# design.net
KiCad netlist of a schematic drawn in Altium Designer
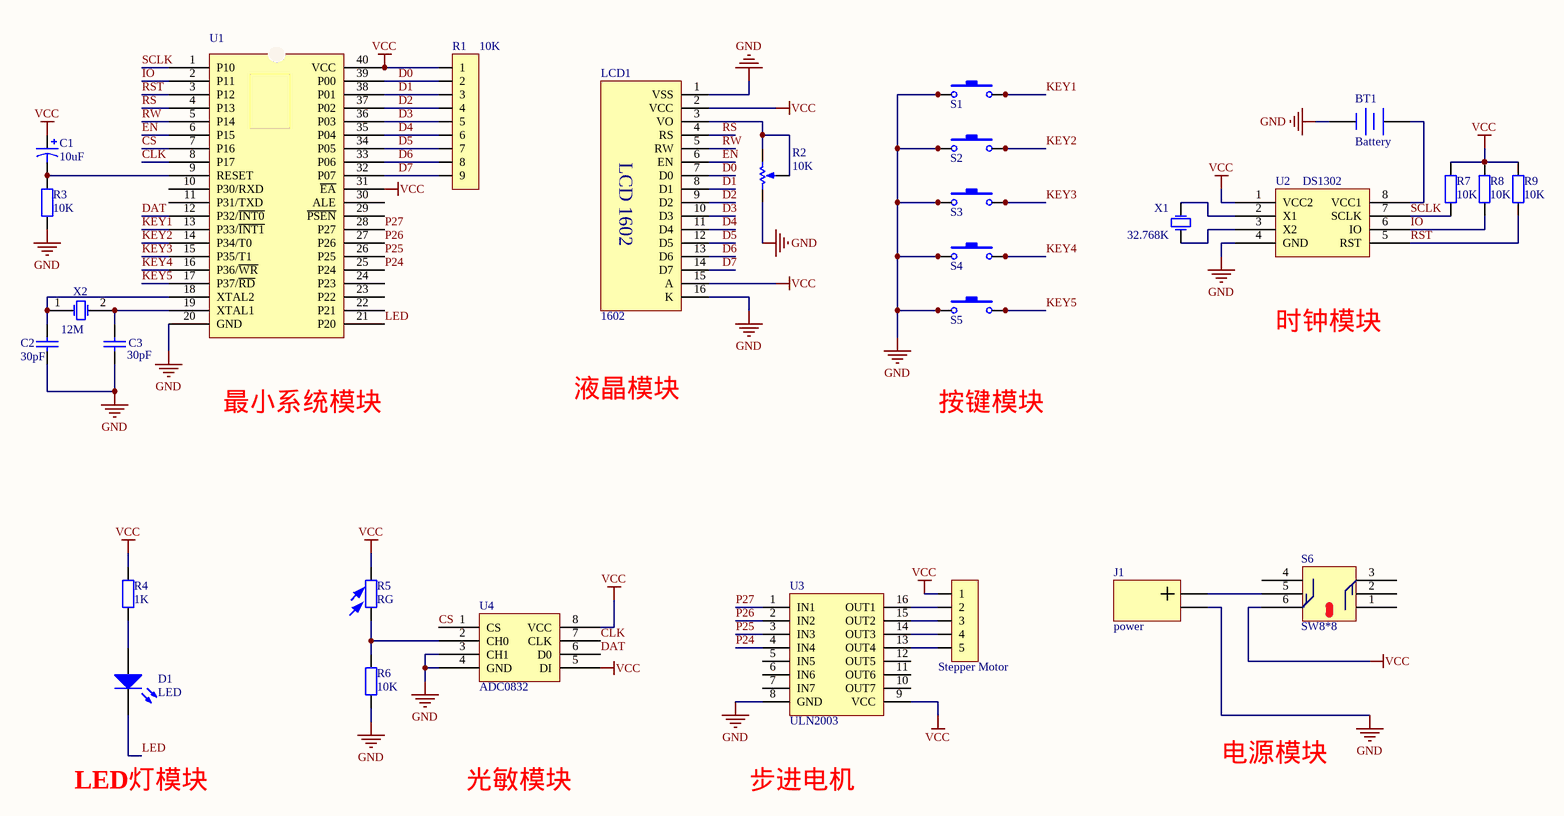
[diagram p0: 硬件电路.SchDoc]

(export (version "E")
  (design (tool "Eeschema 10.0.6"))
  (components
    (comp (ref "BT1")
      (value "Battery")
      (footprint "DCZ--DCBT_3V")
      (libsource (lib "MANUAL") (part "Battery"))
    )
    (comp (ref "C1") (value "10uF") (footprint "DR--CRB-2.54/5MM") (libsource (lib "Schlib") (part "CAP_2")))
    (comp (ref "C2") (value "30pF") (footprint "DR--CCP-4X5") (libsource (lib "Schlib") (part "CAP")))
    (comp (ref "C3") (value "30pF") (footprint "DR--CCP-4X5") (libsource (lib "Schlib") (part "CAP")))
    (comp (ref "D1") (value "LED") (footprint "EJG--LED5mm") (libsource (lib "MANUAL") (part "LED")))
    (comp (ref "J1") (value "power") (footprint "DYZ--DC002") (libsource (lib "Schlib") (part "DC5.5")))
    (comp (ref "J2")
      (value "Stepper Motor")
      (footprint "HDR1X5")
      (libsource (lib "Factory") (part "HEARDER5"))
    )
    (comp (ref "LCD1") (value "1602") (footprint "YJ--LCD1602") (libsource (lib "MANUAL") (part "1602")))
    (comp (ref "R1") (value "10K") (footprint "DZ--Rpz09") (libsource (lib "Schlib") (part "Header9")))
    (comp (ref "R2") (value "10K") (footprint "DZ--R065") (libsource (lib "Schlib") (part "RES-B")))
    (comp (ref "R3") (value "10K") (footprint "DZ--RAXIAL-0.4_D") (libsource (lib "") (part "Res_1")))
    (comp (ref "R4") (value "1K") (footprint "DZ--RAXIAL-0.4_D") (libsource (lib "MANUAL") (part "Res")))
    (comp (ref "R5") (value "RG") (footprint "DZ--RGL5506") (libsource (lib "MANUAL") (part "RG")))
    (comp (ref "R6") (value "10K") (footprint "DZ--RAXIAL-0.4_D") (libsource (lib "MANUAL") (part "Res")))
    (comp (ref "R7") (value "10K") (footprint "DZ--RAXIAL-0.4_D") (libsource (lib "Schlib") (part "Res")))
    (comp (ref "R8") (value "10K") (footprint "DZ--RAXIAL-0.4_D") (libsource (lib "Schlib") (part "Res")))
    (comp (ref "R9") (value "10K") (footprint "DZ--RAXIAL-0.4_D") (libsource (lib "Schlib") (part "Res")))
    (comp (ref "S1")
      (value "AJ--SW-PB")
      (footprint "SW6*6*5")
      (description "Switch")
      (fields (field (name "PUBLISHER") "Altium Limited"))
      (libsource (lib "改别的设计原理图封装") (part "AJ--SW-PB"))
    )
    (comp (ref "S2")
      (value "AJ--SW-PB")
      (footprint "SW6*6*5")
      (description "Switch")
      (fields (field (name "PUBLISHER") "Altium Limited"))
      (libsource (lib "改别的设计原理图封装") (part "AJ--SW-PB"))
    )
    (comp (ref "S3")
      (value "AJ--SW-PB")
      (footprint "SW6*6*5")
      (description "Switch")
      (fields (field (name "PUBLISHER") "Altium Limited"))
      (libsource (lib "改别的设计原理图封装") (part "AJ--SW-PB"))
    )
    (comp (ref "S4")
      (value "AJ--SW-PB")
      (footprint "SW6*6*5")
      (description "Switch")
      (fields (field (name "PUBLISHER") "Altium Limited"))
      (libsource (lib "改别的设计原理图封装") (part "AJ--SW-PB"))
    )
    (comp (ref "S5")
      (value "AJ--SW-PB")
      (footprint "SW6*6*5")
      (description "Switch")
      (fields (field (name "PUBLISHER") "Altium Limited"))
      (libsource (lib "改别的设计原理图封装") (part "AJ--SW-PB"))
    )
    (comp (ref "S6")
      (value "SW8*8")
      (footprint "51单片机最新库 - 拼音排序:KG--SW8*8")
      (description "自锁开关")
      (libsource (lib "51单片机最新库 - 拼音排序") (part "KG--SW8*8"))
    )
    (comp (ref "U1") (value "MCU") (footprint "ICZ--DIP40") (libsource (lib "Schlib") (part "STC89C52")))
    (comp (ref "U2") (value "DS1302") (footprint "ICZ--DIP8") (libsource (lib "MANUAL") (part "DS1302")))
    (comp (ref "U3") (value "ULN2003") (footprint "DIP16") (libsource (lib "Factory") (part "ULN2003")))
    (comp (ref "U4") (value "ADC0832") (footprint "ICZ--DIP8") (libsource (lib "MANUAL") (part "ADC0832")))
    (comp (ref "W")
      (value "WYB--")
      (footprint "51单片机最新库 - 拼音排序:WYB--M9X15cm")
      (description "WYB")
      (libsource (lib "51单片机最新库 - 拼音排序") (part "WYB--"))
    )
    (comp (ref "X1") (value "32.768K") (footprint "JZ--XTAL3") (libsource (lib "Factory") (part "XTAL")))
    (comp (ref "X2") (value "12M") (footprint "JZ--XTAL1") (libsource (lib "Schlib") (part "XTAL")))
  )
  (nets
    (net (code "1") (name "/CLK") (class "Default")
      (node (ref "U1") (pin "8") (pinfunction "P17_8") (pintype "passive"))
      (node (ref "U4") (pin "7") (pinfunction "CLK_7") (pintype "passive"))
    )
    (net (code "2") (name "/CS") (class "Default")
      (node (ref "U1") (pin "7") (pinfunction "P16_7") (pintype "passive"))
      (node (ref "U4") (pin "1") (pinfunction "CS_1") (pintype "passive"))
    )
    (net (code "3") (name "/D0") (class "Default")
      (node (ref "LCD1") (pin "7") (pinfunction "D0_7") (pintype "passive"))
      (node (ref "R1") (pin "2") (pinfunction "2_2") (pintype "passive"))
      (node (ref "U1") (pin "39") (pinfunction "P00_39") (pintype "passive"))
    )
    (net (code "4") (name "/D1") (class "Default")
      (node (ref "LCD1") (pin "8") (pinfunction "D1_8") (pintype "passive"))
      (node (ref "R1") (pin "3") (pinfunction "3_3") (pintype "passive"))
      (node (ref "U1") (pin "38") (pinfunction "P01_38") (pintype "passive"))
    )
    (net (code "5") (name "/D2") (class "Default")
      (node (ref "LCD1") (pin "9") (pinfunction "D2_9") (pintype "passive"))
      (node (ref "R1") (pin "4") (pinfunction "4_4") (pintype "passive"))
      (node (ref "U1") (pin "37") (pinfunction "P02_37") (pintype "passive"))
    )
    (net (code "6") (name "/D3") (class "Default")
      (node (ref "LCD1") (pin "10") (pinfunction "D3_10") (pintype "passive"))
      (node (ref "R1") (pin "5") (pinfunction "5_5") (pintype "passive"))
      (node (ref "U1") (pin "36") (pinfunction "P03_36") (pintype "passive"))
    )
    (net (code "7") (name "/D4") (class "Default")
      (node (ref "LCD1") (pin "11") (pinfunction "D4_11") (pintype "passive"))
      (node (ref "R1") (pin "6") (pinfunction "6_6") (pintype "passive"))
      (node (ref "U1") (pin "35") (pinfunction "P04_35") (pintype "passive"))
    )
    (net (code "8") (name "/D5") (class "Default")
      (node (ref "LCD1") (pin "12") (pinfunction "D5_12") (pintype "passive"))
      (node (ref "R1") (pin "7") (pinfunction "7_7") (pintype "passive"))
      (node (ref "U1") (pin "34") (pinfunction "P05_34") (pintype "passive"))
    )
    (net (code "9") (name "/D6") (class "Default")
      (node (ref "LCD1") (pin "13") (pinfunction "D6_13") (pintype "passive"))
      (node (ref "R1") (pin "8") (pinfunction "8_8") (pintype "passive"))
      (node (ref "U1") (pin "33") (pinfunction "P06_33") (pintype "passive"))
    )
    (net (code "10") (name "/D7") (class "Default")
      (node (ref "LCD1") (pin "14") (pinfunction "D7_14") (pintype "passive"))
      (node (ref "R1") (pin "9") (pinfunction "9_9") (pintype "passive"))
      (node (ref "U1") (pin "32") (pinfunction "P07_32") (pintype "passive"))
    )
    (net (code "11") (name "/DAT") (class "Default")
      (node (ref "U1") (pin "12") (pinfunction "P32/~{INT0}_12") (pintype "passive"))
      (node (ref "U4") (pin "6") (pinfunction "D0_6") (pintype "passive"))
    )
    (net (code "12") (name "/EN") (class "Default")
      (node (ref "LCD1") (pin "6") (pinfunction "EN_6") (pintype "passive"))
      (node (ref "U1") (pin "6") (pinfunction "P15_6") (pintype "passive"))
    )
    (net (code "13") (name "/IO") (class "Default")
      (node (ref "R8") (pin "2") (pinfunction "2_2") (pintype "passive"))
      (node (ref "U1") (pin "2") (pinfunction "P11_2") (pintype "passive"))
      (node (ref "U2") (pin "6") (pinfunction "IO_6") (pintype "passive"))
    )
    (net (code "14") (name "/KEY1") (class "Default")
      (node (ref "S1") (pin "2") (pinfunction "2_2") (pintype "passive"))
      (node (ref "S1") (pin "4") (pinfunction "4_4") (pintype "passive"))
      (node (ref "U1") (pin "13") (pinfunction "P33/~{INT1}_13") (pintype "passive"))
    )
    (net (code "15") (name "/KEY2") (class "Default")
      (node (ref "S2") (pin "2") (pinfunction "2_2") (pintype "passive"))
      (node (ref "S2") (pin "4") (pinfunction "4_4") (pintype "passive"))
      (node (ref "U1") (pin "14") (pinfunction "P34/T0_14") (pintype "passive"))
    )
    (net (code "16") (name "/KEY3") (class "Default")
      (node (ref "S3") (pin "2") (pinfunction "2_2") (pintype "passive"))
      (node (ref "S3") (pin "4") (pinfunction "4_4") (pintype "passive"))
      (node (ref "U1") (pin "15") (pinfunction "P35/T1_15") (pintype "passive"))
    )
    (net (code "17") (name "/KEY4") (class "Default")
      (node (ref "S4") (pin "2") (pinfunction "2_2") (pintype "passive"))
      (node (ref "S4") (pin "4") (pinfunction "4_4") (pintype "passive"))
      (node (ref "U1") (pin "16") (pinfunction "P36/~{WR}_16") (pintype "passive"))
    )
    (net (code "18") (name "/KEY5") (class "Default")
      (node (ref "S5") (pin "2") (pinfunction "2_2") (pintype "passive"))
      (node (ref "S5") (pin "4") (pinfunction "4_4") (pintype "passive"))
      (node (ref "U1") (pin "17") (pinfunction "P37/~{RD}_17") (pintype "passive"))
    )
    (net (code "19") (name "/LED") (class "Default")
      (node (ref "D1") (pin "2") (pinfunction "2_2") (pintype "passive"))
      (node (ref "U1") (pin "21") (pinfunction "P20_21") (pintype "passive"))
    )
    (net (code "20") (name "/P24") (class "Default")
      (node (ref "U1") (pin "25") (pinfunction "P24_25") (pintype "passive"))
      (node (ref "U3") (pin "4") (pinfunction "IN4_4") (pintype "passive"))
    )
    (net (code "21") (name "/P25") (class "Default")
      (node (ref "U1") (pin "26") (pinfunction "P25_26") (pintype "passive"))
      (node (ref "U3") (pin "3") (pinfunction "IN3_3") (pintype "passive"))
    )
    (net (code "22") (name "/P26") (class "Default")
      (node (ref "U1") (pin "27") (pinfunction "P26_27") (pintype "passive"))
      (node (ref "U3") (pin "2") (pinfunction "IN2_2") (pintype "passive"))
    )
    (net (code "23") (name "/P27") (class "Default")
      (node (ref "U1") (pin "28") (pinfunction "P27_28") (pintype "passive"))
      (node (ref "U3") (pin "1") (pinfunction "IN1_1") (pintype "passive"))
    )
    (net (code "24") (name "/RS") (class "Default")
      (node (ref "LCD1") (pin "4") (pinfunction "RS_4") (pintype "passive"))
      (node (ref "U1") (pin "4") (pinfunction "P13_4") (pintype "passive"))
    )
    (net (code "25") (name "/RST") (class "Default")
      (node (ref "R9") (pin "2") (pinfunction "2_2") (pintype "passive"))
      (node (ref "U1") (pin "3") (pinfunction "P12_3") (pintype "passive"))
      (node (ref "U2") (pin "5") (pinfunction "RST_5") (pintype "passive"))
    )
    (net (code "26") (name "/RW") (class "Default")
      (node (ref "LCD1") (pin "5") (pinfunction "RW_5") (pintype "passive"))
      (node (ref "U1") (pin "5") (pinfunction "P14_5") (pintype "passive"))
    )
    (net (code "27") (name "/SCLK") (class "Default")
      (node (ref "R7") (pin "2") (pinfunction "2_2") (pintype "passive"))
      (node (ref "U1") (pin "1") (pinfunction "P10_1") (pintype "passive"))
      (node (ref "U2") (pin "7") (pinfunction "SCLK_7") (pintype "passive"))
    )
    (net (code "28") (name "GND") (class "Default")
      (node (ref "BT1") (pin "2") (pinfunction "-_2") (pintype "passive"))
      (node (ref "C2") (pin "1") (pinfunction "1_1") (pintype "passive"))
      (node (ref "C3") (pin "1") (pinfunction "1_1") (pintype "passive"))
      (node (ref "J1") (pin "2") (pinfunction "2_2") (pintype "passive"))
      (node (ref "LCD1") (pin "1") (pinfunction "VSS_1") (pintype "passive"))
      (node (ref "LCD1") (pin "16") (pinfunction "K_16") (pintype "passive"))
      (node (ref "R2") (pin "1") (pinfunction "1_1") (pintype "passive"))
      (node (ref "R3") (pin "1") (pinfunction "1_1") (pintype "passive"))
      (node (ref "R6") (pin "1") (pinfunction "1_1") (pintype "passive"))
      (node (ref "S1") (pin "1") (pinfunction "1_1") (pintype "passive"))
      (node (ref "S1") (pin "3") (pinfunction "3_3") (pintype "passive"))
      (node (ref "S2") (pin "1") (pinfunction "1_1") (pintype "passive"))
      (node (ref "S2") (pin "3") (pinfunction "3_3") (pintype "passive"))
      (node (ref "S3") (pin "1") (pinfunction "1_1") (pintype "passive"))
      (node (ref "S3") (pin "3") (pinfunction "3_3") (pintype "passive"))
      (node (ref "S4") (pin "1") (pinfunction "1_1") (pintype "passive"))
      (node (ref "S4") (pin "3") (pinfunction "3_3") (pintype "passive"))
      (node (ref "S5") (pin "1") (pinfunction "1_1") (pintype "passive"))
      (node (ref "S5") (pin "3") (pinfunction "3_3") (pintype "passive"))
      (node (ref "U1") (pin "20") (pinfunction "GND_20") (pintype "passive"))
      (node (ref "U2") (pin "4") (pinfunction "GND_4") (pintype "passive"))
      (node (ref "U3") (pin "8") (pinfunction "GND_8") (pintype "passive"))
      (node (ref "U4") (pin "3") (pinfunction "CH1_3") (pintype "passive"))
      (node (ref "U4") (pin "4") (pinfunction "GND_4") (pintype "passive"))
    )
    (net (code "29") (name "Net-(BT1-+)") (class "Default")
      (node (ref "BT1") (pin "1") (pinfunction "+_1") (pintype "passive"))
      (node (ref "U2") (pin "8") (pinfunction "VCC1_8") (pintype "passive"))
    )
    (net (code "30") (name "Net-(D1-Pad1)") (class "Default")
      (node (ref "D1") (pin "1") (pinfunction "1_1") (pintype "passive"))
      (node (ref "R4") (pin "1") (pinfunction "1_1") (pintype "passive"))
    )
    (net (code "31") (name "Net-(J1-Pad1)") (class "Default")
      (node (ref "J1") (pin "1") (pinfunction "1_1") (pintype "passive"))
      (node (ref "S6") (pin "5") (pinfunction "5_5") (pintype "passive"))
    )
    (net (code "32") (name "Net-(LCD1-VO)") (class "Default")
      (node (ref "LCD1") (pin "3") (pinfunction "VO_3") (pintype "passive"))
      (node (ref "R2") (pin "2") (pinfunction "2_2") (pintype "passive"))
      (node (ref "R2") (pin "3") (pinfunction "3_3") (pintype "passive"))
    )
    (net (code "33") (name "Net-(U1-RESET)") (class "Default")
      (node (ref "C1") (pin "2") (pinfunction "2_2") (pintype "passive"))
      (node (ref "R3") (pin "2") (pinfunction "2_2") (pintype "passive"))
      (node (ref "U1") (pin "9") (pinfunction "RESET_9") (pintype "passive"))
    )
    (net (code "34") (name "Net-(U1-XTAL1)") (class "Default")
      (node (ref "C3") (pin "2") (pinfunction "2_2") (pintype "passive"))
      (node (ref "U1") (pin "19") (pinfunction "XTAL1_19") (pintype "passive"))
      (node (ref "X2") (pin "2") (pinfunction "OSC2_2") (pintype "passive"))
    )
    (net (code "35") (name "Net-(U1-XTAL2)") (class "Default")
      (node (ref "C2") (pin "2") (pinfunction "2_2") (pintype "passive"))
      (node (ref "U1") (pin "18") (pinfunction "XTAL2_18") (pintype "passive"))
      (node (ref "X2") (pin "1") (pinfunction "OSC1_1") (pintype "passive"))
    )
    (net (code "36") (name "Net-(U2-X1)") (class "Default")
      (node (ref "U2") (pin "2") (pinfunction "X1_2") (pintype "passive"))
      (node (ref "X1") (pin "2") (pinfunction "OSC2_2") (pintype "passive"))
    )
    (net (code "37") (name "Net-(U2-X2)") (class "Default")
      (node (ref "U2") (pin "3") (pinfunction "X2_3") (pintype "passive"))
      (node (ref "X1") (pin "1") (pinfunction "OSC1_1") (pintype "passive"))
    )
    (net (code "38") (name "Net-(U3-OUT1)") (class "Default")
      (node (ref "J2") (pin "2") (pinfunction "2_2") (pintype "passive"))
      (node (ref "U3") (pin "16") (pinfunction "OUT1_16") (pintype "passive"))
    )
    (net (code "39") (name "Net-(U3-OUT2)") (class "Default")
      (node (ref "J2") (pin "3") (pinfunction "3_3") (pintype "passive"))
      (node (ref "U3") (pin "15") (pinfunction "OUT2_15") (pintype "passive"))
    )
    (net (code "40") (name "Net-(U3-OUT3)") (class "Default")
      (node (ref "J2") (pin "4") (pinfunction "4_4") (pintype "passive"))
      (node (ref "U3") (pin "14") (pinfunction "OUT3_14") (pintype "passive"))
    )
    (net (code "41") (name "Net-(U3-OUT4)") (class "Default")
      (node (ref "J2") (pin "5") (pinfunction "5_5") (pintype "passive"))
      (node (ref "U3") (pin "13") (pinfunction "OUT4_13") (pintype "passive"))
    )
    (net (code "42") (name "Net-(U4-CH0)") (class "Default")
      (node (ref "R5") (pin "1") (pinfunction "1_1") (pintype "passive"))
      (node (ref "R6") (pin "2") (pinfunction "2_2") (pintype "passive"))
      (node (ref "U4") (pin "2") (pinfunction "CH0_2") (pintype "passive"))
    )
    (net (code "43") (name "VCC") (class "Default")
      (node (ref "C1") (pin "1") (pinfunction "1_1") (pintype "passive"))
      (node (ref "J2") (pin "1") (pinfunction "1_1") (pintype "passive"))
      (node (ref "LCD1") (pin "15") (pinfunction "A_15") (pintype "passive"))
      (node (ref "LCD1") (pin "2") (pinfunction "VCC_2") (pintype "passive"))
      (node (ref "R1") (pin "1") (pinfunction "1_1") (pintype "passive"))
      (node (ref "R4") (pin "2") (pinfunction "2_2") (pintype "passive"))
      (node (ref "R5") (pin "2") (pinfunction "2_2") (pintype "passive"))
      (node (ref "R7") (pin "1") (pinfunction "1_1") (pintype "passive"))
      (node (ref "R8") (pin "1") (pinfunction "1_1") (pintype "passive"))
      (node (ref "R9") (pin "1") (pinfunction "1_1") (pintype "passive"))
      (node (ref "S6") (pin "6") (pinfunction "6_6") (pintype "passive"))
      (node (ref "U1") (pin "31") (pinfunction "~{EA}_31") (pintype "passive"))
      (node (ref "U1") (pin "40") (pinfunction "VCC_40") (pintype "passive"))
      (node (ref "U2") (pin "1") (pinfunction "VCC2_1") (pintype "passive"))
      (node (ref "U3") (pin "9") (pinfunction "VCC_9") (pintype "passive"))
      (node (ref "U4") (pin "5") (pinfunction "DI_5") (pintype "passive"))
      (node (ref "U4") (pin "8") (pinfunction "VCC_8") (pintype "passive"))
    )
    (net (code "44") (name "unconnected-(S6-Pad1)") (class "Default")
      (node (ref "S6") (pin "1") (pinfunction "1_1") (pintype "passive"))
    )
    (net (code "45") (name "unconnected-(S6-Pad2)") (class "Default")
      (node (ref "S6") (pin "2") (pinfunction "2_2") (pintype "passive"))
    )
    (net (code "46") (name "unconnected-(S6-Pad3)") (class "Default")
      (node (ref "S6") (pin "3") (pinfunction "3_3") (pintype "passive"))
    )
    (net (code "47") (name "unconnected-(S6-Pad4)") (class "Default")
      (node (ref "S6") (pin "4") (pinfunction "4_4") (pintype "passive"))
    )
    (net (code "48") (name "unconnected-(U1-ALE-Pad30)") (class "Default")
      (node (ref "U1") (pin "30") (pinfunction "ALE_30") (pintype "passive"))
    )
    (net (code "49") (name "unconnected-(U1-P21-Pad22)") (class "Default")
      (node (ref "U1") (pin "22") (pinfunction "P21_22") (pintype "passive"))
    )
    (net (code "50") (name "unconnected-(U1-P22-Pad23)") (class "Default")
      (node (ref "U1") (pin "23") (pinfunction "P22_23") (pintype "passive"))
    )
    (net (code "51") (name "unconnected-(U1-P23-Pad24)") (class "Default")
      (node (ref "U1") (pin "24") (pinfunction "P23_24") (pintype "passive"))
    )
    (net (code "52") (name "unconnected-(U1-P30{slash}RXD-Pad10)") (class "Default")
      (node (ref "U1") (pin "10") (pinfunction "P30/RXD_10") (pintype "passive"))
    )
    (net (code "53") (name "unconnected-(U1-P31{slash}TXD-Pad11)") (class "Default")
      (node (ref "U1") (pin "11") (pinfunction "P31/TXD_11") (pintype "passive"))
    )
    (net (code "54") (name "unconnected-(U1-~{PSEN}-Pad29)") (class "Default")
      (node (ref "U1") (pin "29") (pinfunction "~{PSEN}_29") (pintype "passive"))
    )
    (net (code "55") (name "unconnected-(U3-IN5-Pad5)") (class "Default")
      (node (ref "U3") (pin "5") (pinfunction "IN5_5") (pintype "passive"))
    )
    (net (code "56") (name "unconnected-(U3-IN6-Pad6)") (class "Default")
      (node (ref "U3") (pin "6") (pinfunction "IN6_6") (pintype "passive"))
    )
    (net (code "57") (name "unconnected-(U3-IN7-Pad7)") (class "Default")
      (node (ref "U3") (pin "7") (pinfunction "IN7_7") (pintype "passive"))
    )
    (net (code "58") (name "unconnected-(U3-OUT5-Pad12)") (class "Default")
      (node (ref "U3") (pin "12") (pinfunction "OUT5_12") (pintype "passive"))
    )
    (net (code "59") (name "unconnected-(U3-OUT6-Pad11)") (class "Default")
      (node (ref "U3") (pin "11") (pinfunction "OUT6_11") (pintype "passive"))
    )
    (net (code "60") (name "unconnected-(U3-OUT7-Pad10)") (class "Default")
      (node (ref "U3") (pin "10") (pinfunction "OUT7_10") (pintype "passive"))
    )
  )
)
